# Enchante.net
KiCad netlist of a schematic drawn in Altium Designer
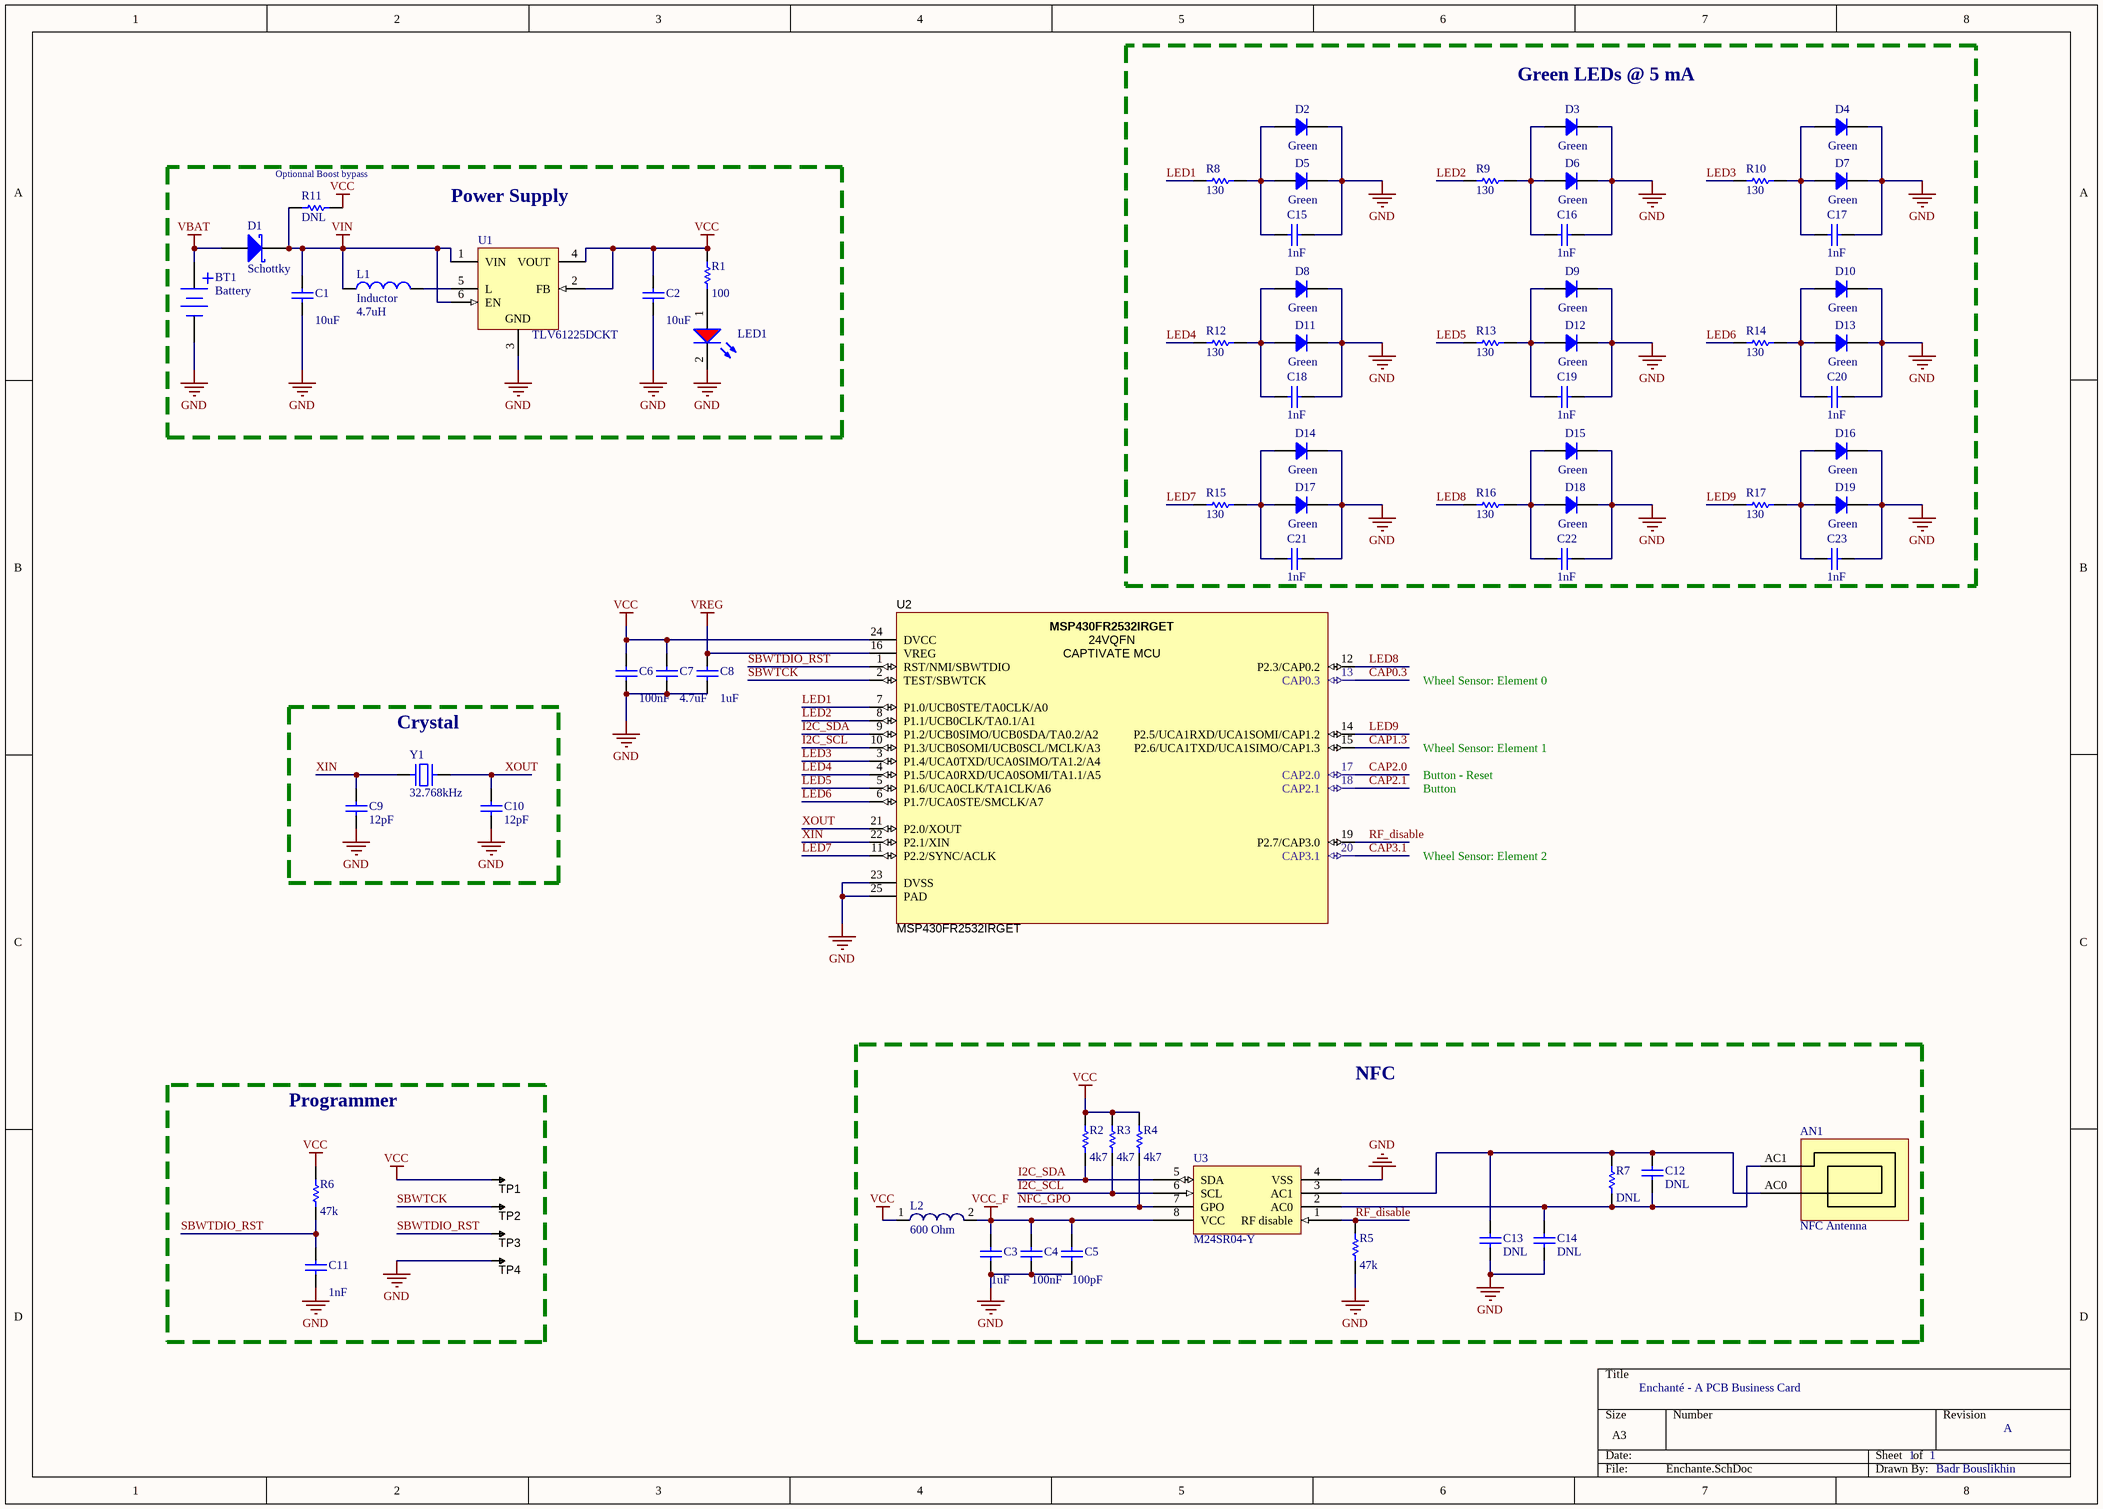
[diagram p0: Enchante.SchDoc]

(export (version "E")
  (design (tool "Eeschema 10.0.6"))
  (components
    (comp (ref "AN1")
      (value "NFC Antenna")
      (footprint "NFC_Antenna")
      (description "L=5.51 uH, tuned for 13.56 MHz")
      (libsource (lib "NFC_Antenna") (part "NFC_Antenna"))
    )
    (comp (ref "BT1")
      (value "Battery")
      (footprint "BC-2001")
      (description "Multicell Battery")
      (libsource (lib "BC-2001") (part "Battery"))
    )
    (comp (ref "C1")
      (value "10uF")
      (footprint "1608[0603]")
      (description "Capacitor")
      (fields (field (name "Comment") "Cap"))
      (libsource (lib "Miscellaneous Devices") (part "Cap"))
    )
    (comp (ref "C2")
      (value "10uF")
      (footprint "1608[0603]")
      (description "Capacitor")
      (fields (field (name "Comment") "Cap"))
      (libsource (lib "Miscellaneous Devices") (part "Cap"))
    )
    (comp (ref "C3")
      (value "1uF")
      (footprint "1608[0603]")
      (description "Capacitor")
      (fields (field (name "Comment") "Cap"))
      (libsource (lib "Miscellaneous Devices") (part "Cap"))
    )
    (comp (ref "C4")
      (value "100nF")
      (footprint "1608[0603]")
      (description "Capacitor")
      (fields (field (name "Comment") "Cap"))
      (libsource (lib "Miscellaneous Devices") (part "Cap"))
    )
    (comp (ref "C5")
      (value "100pF")
      (footprint "1608[0603]")
      (description "Capacitor")
      (fields (field (name "Comment") "Cap"))
      (libsource (lib "Miscellaneous Devices") (part "Cap"))
    )
    (comp (ref "C6")
      (value "100nF")
      (footprint "1608[0603]")
      (description "Capacitor")
      (fields (field (name "Comment") "Cap"))
      (libsource (lib "Miscellaneous Devices") (part "Cap"))
    )
    (comp (ref "C7")
      (value "4.7uF")
      (footprint "1608[0603]")
      (description "Capacitor")
      (fields (field (name "Comment") "Cap"))
      (libsource (lib "Miscellaneous Devices") (part "Cap"))
    )
    (comp (ref "C8")
      (value "1uF")
      (footprint "1608[0603]")
      (description "Capacitor")
      (fields (field (name "Comment") "Cap"))
      (libsource (lib "Miscellaneous Devices") (part "Cap"))
    )
    (comp (ref "C9")
      (value "12pF")
      (footprint "1608[0603]")
      (description "Capacitor")
      (fields (field (name "Comment") "Cap"))
      (libsource (lib "Miscellaneous Devices") (part "Cap"))
    )
    (comp (ref "C10")
      (value "12pF")
      (footprint "1608[0603]")
      (description "Capacitor")
      (fields (field (name "Comment") "Cap"))
      (libsource (lib "Miscellaneous Devices") (part "Cap"))
    )
    (comp (ref "C11")
      (value "1nF")
      (footprint "1608[0603]")
      (description "Capacitor")
      (fields (field (name "Comment") "Cap"))
      (libsource (lib "Miscellaneous Devices") (part "Cap"))
    )
    (comp (ref "C12")
      (value "DNL")
      (footprint "1608[0603]")
      (description "Capacitor")
      (fields (field (name "Comment") "Cap"))
      (libsource (lib "Miscellaneous Devices") (part "Cap"))
    )
    (comp (ref "C13")
      (value "DNL")
      (footprint "1608[0603]")
      (description "Capacitor")
      (fields (field (name "Comment") "Cap"))
      (libsource (lib "Miscellaneous Devices") (part "Cap"))
    )
    (comp (ref "C14")
      (value "DNL")
      (footprint "1608[0603]")
      (description "Capacitor")
      (fields (field (name "Comment") "Cap"))
      (libsource (lib "Miscellaneous Devices") (part "Cap"))
    )
    (comp (ref "C15")
      (value "1nF")
      (footprint "1608[0603]")
      (description "Capacitor")
      (fields (field (name "Comment") "Cap"))
      (libsource (lib "Miscellaneous Devices") (part "Cap"))
    )
    (comp (ref "C16")
      (value "1nF")
      (footprint "1608[0603]")
      (description "Capacitor")
      (fields (field (name "Comment") "Cap"))
      (libsource (lib "Miscellaneous Devices") (part "Cap"))
    )
    (comp (ref "C17")
      (value "1nF")
      (footprint "1608[0603]")
      (description "Capacitor")
      (fields (field (name "Comment") "Cap"))
      (libsource (lib "Miscellaneous Devices") (part "Cap"))
    )
    (comp (ref "C18")
      (value "1nF")
      (footprint "1608[0603]")
      (description "Capacitor")
      (fields (field (name "Comment") "Cap"))
      (libsource (lib "Miscellaneous Devices") (part "Cap"))
    )
    (comp (ref "C19")
      (value "1nF")
      (footprint "1608[0603]")
      (description "Capacitor")
      (fields (field (name "Comment") "Cap"))
      (libsource (lib "Miscellaneous Devices") (part "Cap"))
    )
    (comp (ref "C20")
      (value "1nF")
      (footprint "1608[0603]")
      (description "Capacitor")
      (fields (field (name "Comment") "Cap"))
      (libsource (lib "Miscellaneous Devices") (part "Cap"))
    )
    (comp (ref "C21")
      (value "1nF")
      (footprint "1608[0603]")
      (description "Capacitor")
      (fields (field (name "Comment") "Cap"))
      (libsource (lib "Miscellaneous Devices") (part "Cap"))
    )
    (comp (ref "C22")
      (value "1nF")
      (footprint "1608[0603]")
      (description "Capacitor")
      (fields (field (name "Comment") "Cap"))
      (libsource (lib "Miscellaneous Devices") (part "Cap"))
    )
    (comp (ref "C23")
      (value "1nF")
      (footprint "1608[0603]")
      (description "Capacitor")
      (fields (field (name "Comment") "Cap"))
      (libsource (lib "Miscellaneous Devices") (part "Cap"))
    )
    (comp (ref "D1")
      (value "Schottky")
      (footprint "SOT23_N")
      (description "Schottky Diode")
      (libsource (lib "Miscellaneous Devices") (part "D Schottky"))
    )
    (comp (ref "D2")
      (value "1318243")
      (footprint "LED 0805/2012 GREEN")
      (description "Rectifier Diode")
      (fields (field (name "COLOR") "Green"))
      (libsource (lib "Diodes") (part "Diode"))
    )
    (comp (ref "D3")
      (value "1318243")
      (footprint "LED 0805/2012 GREEN")
      (description "Rectifier Diode")
      (fields (field (name "COLOR") "Green"))
      (libsource (lib "Diodes") (part "Diode"))
    )
    (comp (ref "D4")
      (value "1318243")
      (footprint "LED 0805/2012 GREEN")
      (description "Rectifier Diode")
      (fields (field (name "COLOR") "Green"))
      (libsource (lib "Diodes") (part "Diode"))
    )
    (comp (ref "D5")
      (value "1318243")
      (footprint "LED 0805/2012 GREEN")
      (description "Rectifier Diode")
      (fields (field (name "COLOR") "Green"))
      (libsource (lib "Diodes") (part "Diode"))
    )
    (comp (ref "D6")
      (value "1318243")
      (footprint "LED 0805/2012 GREEN")
      (description "Rectifier Diode")
      (fields (field (name "COLOR") "Green"))
      (libsource (lib "Diodes") (part "Diode"))
    )
    (comp (ref "D7")
      (value "1318243")
      (footprint "LED 0805/2012 GREEN")
      (description "Rectifier Diode")
      (fields (field (name "COLOR") "Green"))
      (libsource (lib "Diodes") (part "Diode"))
    )
    (comp (ref "D8")
      (value "1318243")
      (footprint "LED 0805/2012 GREEN")
      (description "Rectifier Diode")
      (fields (field (name "COLOR") "Green"))
      (libsource (lib "Diodes") (part "Diode"))
    )
    (comp (ref "D9")
      (value "1318243")
      (footprint "LED 0805/2012 GREEN")
      (description "Rectifier Diode")
      (fields (field (name "COLOR") "Green"))
      (libsource (lib "Diodes") (part "Diode"))
    )
    (comp (ref "D10")
      (value "1318243")
      (footprint "LED 0805/2012 GREEN")
      (description "Rectifier Diode")
      (fields (field (name "COLOR") "Green"))
      (libsource (lib "Diodes") (part "Diode"))
    )
    (comp (ref "D11")
      (value "1318243")
      (footprint "LED 0805/2012 GREEN")
      (description "Rectifier Diode")
      (fields (field (name "COLOR") "Green"))
      (libsource (lib "Diodes") (part "Diode"))
    )
    (comp (ref "D12")
      (value "1318243")
      (footprint "LED 0805/2012 GREEN")
      (description "Rectifier Diode")
      (fields (field (name "COLOR") "Green"))
      (libsource (lib "Diodes") (part "Diode"))
    )
    (comp (ref "D13")
      (value "1318243")
      (footprint "LED 0805/2012 GREEN")
      (description "Rectifier Diode")
      (fields (field (name "COLOR") "Green"))
      (libsource (lib "Diodes") (part "Diode"))
    )
    (comp (ref "D14")
      (value "1318243")
      (footprint "LED 0805/2012 GREEN")
      (description "Rectifier Diode")
      (fields (field (name "COLOR") "Green"))
      (libsource (lib "Diodes") (part "Diode"))
    )
    (comp (ref "D15")
      (value "1318243")
      (footprint "LED 0805/2012 GREEN")
      (description "Rectifier Diode")
      (fields (field (name "COLOR") "Green"))
      (libsource (lib "Diodes") (part "Diode"))
    )
    (comp (ref "D16")
      (value "1318243")
      (footprint "LED 0805/2012 GREEN")
      (description "Rectifier Diode")
      (fields (field (name "COLOR") "Green"))
      (libsource (lib "Diodes") (part "Diode"))
    )
    (comp (ref "D17")
      (value "1318243")
      (footprint "LED 0805/2012 GREEN")
      (description "Rectifier Diode")
      (fields (field (name "COLOR") "Green"))
      (libsource (lib "Diodes") (part "Diode"))
    )
    (comp (ref "D18")
      (value "1318243")
      (footprint "LED 0805/2012 GREEN")
      (description "Rectifier Diode")
      (fields (field (name "COLOR") "Green"))
      (libsource (lib "Diodes") (part "Diode"))
    )
    (comp (ref "D19")
      (value "1318243")
      (footprint "LED 0805/2012 GREEN")
      (description "Rectifier Diode")
      (fields (field (name "COLOR") "Green"))
      (libsource (lib "Diodes") (part "Diode"))
    )
    (comp (ref "L1")
      (value "Inductor")
      (footprint "VLS2010E")
      (fields (field (name "ALTIUM_VALUE") "4.7uH"))
      (libsource (lib "Miscellaneous Devices") (part "Inductor"))
    )
    (comp (ref "L2")
      (value "600 Ohm")
      (footprint "SMD 0805")
      (description "SMD EMI Suppression Ferrite Beads WE-CBF, Z= 600 Ohm")
      (fields
        (field (name "PARTNO") "742792042")
        (field (name "MANUFACTURER") "Würth Elektronik eiSos GmbH")
        (field (name "CREATED BY") "Christin Zierenner")
      )
      (libsource (lib "WE-CBF_rev15a") (part "WE-CBF 0805, 742792042"))
    )
    (comp (ref "LED1")
      (value "150060RS75000")
      (footprint "LED_0603_Red")
      (description "SMD mono-color Chip LED, WL-SMCW, Red")
      (fields
        (field (name "MANUFACTURER") "W黵th Elektronik eiSos GmbH")
        (field (name "CREATED BY") "Christin Otto")
      )
      (libsource (lib "WL-SMCW_rev15b") (part "WL-SMCW 0603  150060RS75000"))
    )
    (comp (ref "R1")
      (value "100")
      (footprint "J1-0603")
      (description "Resistor")
      (fields (field (name "Comment") "Res1"))
      (libsource (lib "Miscellaneous Devices") (part "Res1"))
    )
    (comp (ref "R2")
      (value "4k7")
      (footprint "J1-0603")
      (description "Resistor")
      (fields (field (name "Comment") "Res1"))
      (libsource (lib "Miscellaneous Devices") (part "Res1"))
    )
    (comp (ref "R3")
      (value "4k7")
      (footprint "J1-0603")
      (description "Resistor")
      (fields (field (name "Comment") "Res1"))
      (libsource (lib "Miscellaneous Devices") (part "Res1"))
    )
    (comp (ref "R4")
      (value "4k7")
      (footprint "J1-0603")
      (description "Resistor")
      (fields (field (name "Comment") "Res1"))
      (libsource (lib "Miscellaneous Devices") (part "Res1"))
    )
    (comp (ref "R5")
      (value "47k")
      (footprint "J1-0603")
      (description "Resistor")
      (fields (field (name "Comment") "Res1"))
      (libsource (lib "Miscellaneous Devices") (part "Res1"))
    )
    (comp (ref "R6")
      (value "47k")
      (footprint "J1-0603")
      (description "Resistor")
      (fields (field (name "Comment") "Res1"))
      (libsource (lib "Miscellaneous Devices") (part "Res1"))
    )
    (comp (ref "R7")
      (value "DNL")
      (footprint "J1-0603")
      (description "Resistor")
      (fields (field (name "Comment") "Res1"))
      (libsource (lib "Miscellaneous Devices") (part "Res1"))
    )
    (comp (ref "R8")
      (value "130")
      (footprint "J1-0603")
      (description "Resistor")
      (fields (field (name "Comment") "Res1"))
      (libsource (lib "Miscellaneous Devices") (part "Res1"))
    )
    (comp (ref "R9")
      (value "130")
      (footprint "J1-0603")
      (description "Resistor")
      (fields (field (name "Comment") "Res1"))
      (libsource (lib "Miscellaneous Devices") (part "Res1"))
    )
    (comp (ref "R10")
      (value "130")
      (footprint "J1-0603")
      (description "Resistor")
      (fields (field (name "Comment") "Res1"))
      (libsource (lib "Miscellaneous Devices") (part "Res1"))
    )
    (comp (ref "R11")
      (value "DNL")
      (footprint "J1-0603")
      (description "Resistor")
      (fields (field (name "Comment") "Res1"))
      (libsource (lib "Miscellaneous Devices") (part "Res1"))
    )
    (comp (ref "R12")
      (value "130")
      (footprint "J1-0603")
      (description "Resistor")
      (fields (field (name "Comment") "Res1"))
      (libsource (lib "Miscellaneous Devices") (part "Res1"))
    )
    (comp (ref "R13")
      (value "130")
      (footprint "J1-0603")
      (description "Resistor")
      (fields (field (name "Comment") "Res1"))
      (libsource (lib "Miscellaneous Devices") (part "Res1"))
    )
    (comp (ref "R14")
      (value "130")
      (footprint "J1-0603")
      (description "Resistor")
      (fields (field (name "Comment") "Res1"))
      (libsource (lib "Miscellaneous Devices") (part "Res1"))
    )
    (comp (ref "R15")
      (value "130")
      (footprint "J1-0603")
      (description "Resistor")
      (fields (field (name "Comment") "Res1"))
      (libsource (lib "Miscellaneous Devices") (part "Res1"))
    )
    (comp (ref "R16")
      (value "130")
      (footprint "J1-0603")
      (description "Resistor")
      (fields (field (name "Comment") "Res1"))
      (libsource (lib "Miscellaneous Devices") (part "Res1"))
    )
    (comp (ref "R17")
      (value "130")
      (footprint "J1-0603")
      (description "Resistor")
      (fields (field (name "Comment") "Res1"))
      (libsource (lib "Miscellaneous Devices") (part "Res1"))
    )
    (comp (ref "TP1")
      (value "TESTPOINT")
      (footprint "TP-R60")
      (description "SMD test pin")
      (libsource (lib "PBL - Test Points") (part "TESTPOINT"))
    )
    (comp (ref "TP2")
      (value "TESTPOINT")
      (footprint "TP-R60")
      (description "SMD test pin")
      (libsource (lib "PBL - Test Points") (part "TESTPOINT"))
    )
    (comp (ref "TP3")
      (value "TESTPOINT")
      (footprint "TP-R60")
      (description "SMD test pin")
      (libsource (lib "PBL - Test Points") (part "TESTPOINT"))
    )
    (comp (ref "TP4")
      (value "TESTPOINT")
      (footprint "TP-R60")
      (description "SMD test pin")
      (libsource (lib "PBL - Test Points") (part "TESTPOINT"))
    )
    (comp (ref "U1")
      (value "TLV61225DCKT")
      (footprint "DCK0006A_M")
      (fields (field (name "MANUFACTURER") "Texas Instruments"))
      (libsource (lib "Altium Content Vault") (part "CMP-0343-00078-2"))
    )
    (comp (ref "U2")
      (value "MSP430FR2532IRGET")
      (footprint "RGE24_N")
      (description "MSP430 Captivate Microcontroller")
      (fields (field (name "MANUFACTURER") "Texas Instruments") (field (name "SYMBOLCREATOR") "B.B."))
      (libsource (lib "MSP430FR2532") (part "MSP430FR2532IRGET"))
    )
    (comp (ref "U3")
      (value "M24SR04-Y")
      (footprint "ST TSSOP-8")
      (description "Dynamic NFC/RFID tag IC with 4-Kbit EEPROM,   NFC Forum Type 4 Tag and I²C interface")
      (libsource (lib "M24SR04-Y") (part "M24SR04-Y"))
    )
    (comp (ref "Y1")
      (value "32.768kHz")
      (footprint "ABRACON ABS25")
      (description "SMT Crystal")
      (libsource (lib "Crystals") (part "Abracon Crystal ABS25"))
    )
  )
  (nets
    (net (code "1") (name "/CAP0.3") (class "Default")
      (node (ref "U2") (pin "13") (pinfunction "CAP0.3_13") (pintype "bidirectional"))
    )
    (net (code "2") (name "/CAP1.3") (class "Default")
      (node (ref "U2") (pin "15") (pinfunction "P2.6/UCA1TXD/UCA1SIMO/CAP1.3_15") (pintype "bidirectional"))
    )
    (net (code "3") (name "/CAP2.0") (class "Default")
      (node (ref "U2") (pin "17") (pinfunction "CAP2.0_17") (pintype "bidirectional"))
    )
    (net (code "4") (name "/CAP2.1") (class "Default")
      (node (ref "U2") (pin "18") (pinfunction "CAP2.1_18") (pintype "bidirectional"))
    )
    (net (code "5") (name "/CAP3.1") (class "Default")
      (node (ref "U2") (pin "20") (pinfunction "CAP3.1_20") (pintype "bidirectional"))
    )
    (net (code "6") (name "/I2C_SCL") (class "Default")
      (node (ref "R3") (pin "1") (pinfunction "1_1") (pintype "passive"))
      (node (ref "U2") (pin "10") (pinfunction "P1.3/UCB0SOMI/UCB0SCL/MCLK/A3_10") (pintype "bidirectional"))
      (node (ref "U3") (pin "6") (pinfunction "SCL_6") (pintype "input"))
    )
    (net (code "7") (name "/I2C_SDA") (class "Default")
      (node (ref "R2") (pin "1") (pinfunction "1_1") (pintype "passive"))
      (node (ref "U2") (pin "9") (pinfunction "P1.2/UCB0SIMO/UCB0SDA/TA0.2/A2_9") (pintype "bidirectional"))
      (node (ref "U3") (pin "5") (pinfunction "SDA_5") (pintype "bidirectional"))
    )
    (net (code "8") (name "/LED1") (class "Default")
      (node (ref "R8") (pin "2") (pinfunction "2_2") (pintype "passive"))
      (node (ref "U2") (pin "7") (pinfunction "P1.0/UCB0STE/TA0CLK/A0_7") (pintype "bidirectional"))
    )
    (net (code "9") (name "/LED2") (class "Default")
      (node (ref "R9") (pin "2") (pinfunction "2_2") (pintype "passive"))
      (node (ref "U2") (pin "8") (pinfunction "P1.1/UCB0CLK/TA0.1/A1_8") (pintype "bidirectional"))
    )
    (net (code "10") (name "/LED3") (class "Default")
      (node (ref "R10") (pin "2") (pinfunction "2_2") (pintype "passive"))
      (node (ref "U2") (pin "3") (pinfunction "P1.4/UCA0TXD/UCA0SIMO/TA1.2/A4_3") (pintype "bidirectional"))
    )
    (net (code "11") (name "/LED4") (class "Default")
      (node (ref "R12") (pin "2") (pinfunction "2_2") (pintype "passive"))
      (node (ref "U2") (pin "4") (pinfunction "P1.5/UCA0RXD/UCA0SOMI/TA1.1/A5_4") (pintype "bidirectional"))
    )
    (net (code "12") (name "/LED5") (class "Default")
      (node (ref "R13") (pin "2") (pinfunction "2_2") (pintype "passive"))
      (node (ref "U2") (pin "5") (pinfunction "P1.6/UCA0CLK/TA1CLK/A6_5") (pintype "bidirectional"))
    )
    (net (code "13") (name "/LED6") (class "Default")
      (node (ref "R14") (pin "2") (pinfunction "2_2") (pintype "passive"))
      (node (ref "U2") (pin "6") (pinfunction "P1.7/UCA0STE/SMCLK/A7_6") (pintype "bidirectional"))
    )
    (net (code "14") (name "/LED7") (class "Default")
      (node (ref "R15") (pin "2") (pinfunction "2_2") (pintype "passive"))
      (node (ref "U2") (pin "11") (pinfunction "P2.2/SYNC/ACLK_11") (pintype "bidirectional"))
    )
    (net (code "15") (name "/LED8") (class "Default")
      (node (ref "R16") (pin "2") (pinfunction "2_2") (pintype "passive"))
      (node (ref "U2") (pin "12") (pinfunction "P2.3/CAP0.2_12") (pintype "bidirectional"))
    )
    (net (code "16") (name "/LED9") (class "Default")
      (node (ref "R17") (pin "2") (pinfunction "2_2") (pintype "passive"))
      (node (ref "U2") (pin "14") (pinfunction "P2.5/UCA1RXD/UCA1SOMI/CAP1.2_14") (pintype "bidirectional"))
    )
    (net (code "17") (name "/NFC_GPO") (class "Default")
      (node (ref "R4") (pin "1") (pinfunction "1_1") (pintype "passive"))
      (node (ref "U3") (pin "7") (pinfunction "GPO_7") (pintype "passive"))
    )
    (net (code "18") (name "/RF_disable") (class "Default")
      (node (ref "R5") (pin "2") (pinfunction "2_2") (pintype "passive"))
      (node (ref "U2") (pin "19") (pinfunction "P2.7/CAP3.0_19") (pintype "bidirectional"))
      (node (ref "U3") (pin "1") (pinfunction "RF_disable_1") (pintype "input"))
    )
    (net (code "19") (name "/SBWTCK") (class "Default")
      (node (ref "TP2") (pin "1") (pintype "passive"))
      (node (ref "U2") (pin "2") (pinfunction "TEST/SBWTCK_2") (pintype "bidirectional"))
    )
    (net (code "20") (name "/SBWTDIO_RST") (class "Default")
      (node (ref "C11") (pin "2") (pinfunction "2_2") (pintype "passive"))
      (node (ref "R6") (pin "1") (pinfunction "1_1") (pintype "passive"))
      (node (ref "TP3") (pin "1") (pintype "passive"))
      (node (ref "U2") (pin "1") (pinfunction "RST/NMI/SBWTDIO_1") (pintype "bidirectional"))
    )
    (net (code "21") (name "/XIN") (class "Default")
      (node (ref "C9") (pin "2") (pinfunction "2_2") (pintype "passive"))
      (node (ref "U2") (pin "22") (pinfunction "P2.1/XIN_22") (pintype "bidirectional"))
      (node (ref "Y1") (pin "1") (pinfunction "1_1") (pintype "passive"))
    )
    (net (code "22") (name "/XOUT") (class "Default")
      (node (ref "C10") (pin "2") (pinfunction "2_2") (pintype "passive"))
      (node (ref "U2") (pin "21") (pinfunction "P2.0/XOUT_21") (pintype "bidirectional"))
      (node (ref "Y1") (pin "4") (pinfunction "4_4") (pintype "passive"))
    )
    (net (code "23") (name "GND") (class "Default")
      (node (ref "BT1") (pin "2") (pinfunction "-_2") (pintype "passive"))
      (node (ref "C1") (pin "1") (pinfunction "1_1") (pintype "passive"))
      (node (ref "C10") (pin "1") (pinfunction "1_1") (pintype "passive"))
      (node (ref "C11") (pin "1") (pinfunction "1_1") (pintype "passive"))
      (node (ref "C13") (pin "1") (pinfunction "1_1") (pintype "passive"))
      (node (ref "C14") (pin "1") (pinfunction "1_1") (pintype "passive"))
      (node (ref "C15") (pin "1") (pinfunction "1_1") (pintype "passive"))
      (node (ref "C16") (pin "1") (pinfunction "1_1") (pintype "passive"))
      (node (ref "C17") (pin "1") (pinfunction "1_1") (pintype "passive"))
      (node (ref "C18") (pin "1") (pinfunction "1_1") (pintype "passive"))
      (node (ref "C19") (pin "1") (pinfunction "1_1") (pintype "passive"))
      (node (ref "C2") (pin "1") (pinfunction "1_1") (pintype "passive"))
      (node (ref "C20") (pin "1") (pinfunction "1_1") (pintype "passive"))
      (node (ref "C21") (pin "1") (pinfunction "1_1") (pintype "passive"))
      (node (ref "C22") (pin "1") (pinfunction "1_1") (pintype "passive"))
      (node (ref "C23") (pin "1") (pinfunction "1_1") (pintype "passive"))
      (node (ref "C3") (pin "1") (pinfunction "1_1") (pintype "passive"))
      (node (ref "C4") (pin "1") (pinfunction "1_1") (pintype "passive"))
      (node (ref "C5") (pin "1") (pinfunction "1_1") (pintype "passive"))
      (node (ref "C6") (pin "1") (pinfunction "1_1") (pintype "passive"))
      (node (ref "C7") (pin "1") (pinfunction "1_1") (pintype "passive"))
      (node (ref "C8") (pin "1") (pinfunction "1_1") (pintype "passive"))
      (node (ref "C9") (pin "1") (pinfunction "1_1") (pintype "passive"))
      (node (ref "D10") (pin "2") (pinfunction "2_2") (pintype "passive"))
      (node (ref "D11") (pin "2") (pinfunction "2_2") (pintype "passive"))
      (node (ref "D12") (pin "2") (pinfunction "2_2") (pintype "passive"))
      (node (ref "D13") (pin "2") (pinfunction "2_2") (pintype "passive"))
      (node (ref "D14") (pin "2") (pinfunction "2_2") (pintype "passive"))
      (node (ref "D15") (pin "2") (pinfunction "2_2") (pintype "passive"))
      (node (ref "D16") (pin "2") (pinfunction "2_2") (pintype "passive"))
      (node (ref "D17") (pin "2") (pinfunction "2_2") (pintype "passive"))
      (node (ref "D18") (pin "2") (pinfunction "2_2") (pintype "passive"))
      (node (ref "D19") (pin "2") (pinfunction "2_2") (pintype "passive"))
      (node (ref "D2") (pin "2") (pinfunction "2_2") (pintype "passive"))
      (node (ref "D3") (pin "2") (pinfunction "2_2") (pintype "passive"))
      (node (ref "D4") (pin "2") (pinfunction "2_2") (pintype "passive"))
      (node (ref "D5") (pin "2") (pinfunction "2_2") (pintype "passive"))
      (node (ref "D6") (pin "2") (pinfunction "2_2") (pintype "passive"))
      (node (ref "D7") (pin "2") (pinfunction "2_2") (pintype "passive"))
      (node (ref "D8") (pin "2") (pinfunction "2_2") (pintype "passive"))
      (node (ref "D9") (pin "2") (pinfunction "2_2") (pintype "passive"))
      (node (ref "LED1") (pin "2") (pinfunction "C_2") (pintype "passive"))
      (node (ref "R5") (pin "1") (pinfunction "1_1") (pintype "passive"))
      (node (ref "TP4") (pin "1") (pintype "passive"))
      (node (ref "U1") (pin "3") (pinfunction "GND_3") (pintype "power_in"))
      (node (ref "U2") (pin "23") (pinfunction "DVSS_23") (pintype "power_in"))
      (node (ref "U2") (pin "25") (pinfunction "PAD_25") (pintype "power_in"))
      (node (ref "U3") (pin "4") (pinfunction "VSS_4") (pintype "power_in"))
    )
    (net (code "24") (name "Net-(C15-Pad2)") (class "Default")
      (node (ref "C15") (pin "2") (pinfunction "2_2") (pintype "passive"))
      (node (ref "D2") (pin "1") (pinfunction "1_1") (pintype "passive"))
      (node (ref "D5") (pin "1") (pinfunction "1_1") (pintype "passive"))
      (node (ref "R8") (pin "1") (pinfunction "1_1") (pintype "passive"))
    )
    (net (code "25") (name "Net-(C16-Pad2)") (class "Default")
      (node (ref "C16") (pin "2") (pinfunction "2_2") (pintype "passive"))
      (node (ref "D3") (pin "1") (pinfunction "1_1") (pintype "passive"))
      (node (ref "D6") (pin "1") (pinfunction "1_1") (pintype "passive"))
      (node (ref "R9") (pin "1") (pinfunction "1_1") (pintype "passive"))
    )
    (net (code "26") (name "Net-(C17-Pad2)") (class "Default")
      (node (ref "C17") (pin "2") (pinfunction "2_2") (pintype "passive"))
      (node (ref "D4") (pin "1") (pinfunction "1_1") (pintype "passive"))
      (node (ref "D7") (pin "1") (pinfunction "1_1") (pintype "passive"))
      (node (ref "R10") (pin "1") (pinfunction "1_1") (pintype "passive"))
    )
    (net (code "27") (name "Net-(C18-Pad2)") (class "Default")
      (node (ref "C18") (pin "2") (pinfunction "2_2") (pintype "passive"))
      (node (ref "D11") (pin "1") (pinfunction "1_1") (pintype "passive"))
      (node (ref "D8") (pin "1") (pinfunction "1_1") (pintype "passive"))
      (node (ref "R12") (pin "1") (pinfunction "1_1") (pintype "passive"))
    )
    (net (code "28") (name "Net-(C19-Pad2)") (class "Default")
      (node (ref "C19") (pin "2") (pinfunction "2_2") (pintype "passive"))
      (node (ref "D12") (pin "1") (pinfunction "1_1") (pintype "passive"))
      (node (ref "D9") (pin "1") (pinfunction "1_1") (pintype "passive"))
      (node (ref "R13") (pin "1") (pinfunction "1_1") (pintype "passive"))
    )
    (net (code "29") (name "Net-(C20-Pad2)") (class "Default")
      (node (ref "C20") (pin "2") (pinfunction "2_2") (pintype "passive"))
      (node (ref "D10") (pin "1") (pinfunction "1_1") (pintype "passive"))
      (node (ref "D13") (pin "1") (pinfunction "1_1") (pintype "passive"))
      (node (ref "R14") (pin "1") (pinfunction "1_1") (pintype "passive"))
    )
    (net (code "30") (name "Net-(C21-Pad2)") (class "Default")
      (node (ref "C21") (pin "2") (pinfunction "2_2") (pintype "passive"))
      (node (ref "D14") (pin "1") (pinfunction "1_1") (pintype "passive"))
      (node (ref "D17") (pin "1") (pinfunction "1_1") (pintype "passive"))
      (node (ref "R15") (pin "1") (pinfunction "1_1") (pintype "passive"))
    )
    (net (code "31") (name "Net-(C22-Pad2)") (class "Default")
      (node (ref "C22") (pin "2") (pinfunction "2_2") (pintype "passive"))
      (node (ref "D15") (pin "1") (pinfunction "1_1") (pintype "passive"))
      (node (ref "D18") (pin "1") (pinfunction "1_1") (pintype "passive"))
      (node (ref "R16") (pin "1") (pinfunction "1_1") (pintype "passive"))
    )
    (net (code "32") (name "Net-(C23-Pad2)") (class "Default")
      (node (ref "C23") (pin "2") (pinfunction "2_2") (pintype "passive"))
      (node (ref "D16") (pin "1") (pinfunction "1_1") (pintype "passive"))
      (node (ref "D19") (pin "1") (pinfunction "1_1") (pintype "passive"))
      (node (ref "R17") (pin "1") (pinfunction "1_1") (pintype "passive"))
    )
    (net (code "33") (name "Net-(LED1-A)") (class "Default")
      (node (ref "LED1") (pin "1") (pinfunction "A_1") (pintype "passive"))
      (node (ref "R1") (pin "1") (pinfunction "1_1") (pintype "passive"))
    )
    (net (code "34") (name "Net-(U1-L)") (class "Default")
      (node (ref "L1") (pin "2") (pinfunction "2_2") (pintype "passive"))
      (node (ref "U1") (pin "5") (pinfunction "L_5") (pintype "power_in"))
    )
    (net (code "35") (name "Net-(U3-AC0)") (class "Default")
      (node (ref "AN1") (pin "AC1") (pintype "passive"))
      (node (ref "C12") (pin "1") (pinfunction "1_1") (pintype "passive"))
      (node (ref "C14") (pin "2") (pinfunction "2_2") (pintype "passive"))
      (node (ref "R7") (pin "1") (pinfunction "1_1") (pintype "passive"))
      (node (ref "U3") (pin "2") (pinfunction "AC0_2") (pintype "passive"))
    )
    (net (code "36") (name "Net-(U3-AC1)") (class "Default")
      (node (ref "AN1") (pin "AC0") (pintype "passive"))
      (node (ref "C12") (pin "2") (pinfunction "2_2") (pintype "passive"))
      (node (ref "C13") (pin "2") (pinfunction "2_2") (pintype "passive"))
      (node (ref "R7") (pin "2") (pinfunction "2_2") (pintype "passive"))
      (node (ref "U3") (pin "3") (pinfunction "AC1_3") (pintype "passive"))
    )
    (net (code "37") (name "VBAT") (class "Default")
      (node (ref "BT1") (pin "1") (pinfunction "+_1") (pintype "passive"))
      (node (ref "D1") (pin "1") (pinfunction "A_1") (pintype "passive"))
    )
    (net (code "38") (name "VCC") (class "Default")
      (node (ref "C2") (pin "2") (pinfunction "2_2") (pintype "passive"))
      (node (ref "C6") (pin "2") (pinfunction "2_2") (pintype "passive"))
      (node (ref "C7") (pin "2") (pinfunction "2_2") (pintype "passive"))
      (node (ref "L2") (pin "1") (pinfunction "1_1") (pintype "passive"))
      (node (ref "R1") (pin "2") (pinfunction "2_2") (pintype "passive"))
      (node (ref "R11") (pin "1") (pinfunction "1_1") (pintype "passive"))
      (node (ref "R2") (pin "2") (pinfunction "2_2") (pintype "passive"))
      (node (ref "R3") (pin "2") (pinfunction "2_2") (pintype "passive"))
      (node (ref "R4") (pin "2") (pinfunction "2_2") (pintype "passive"))
      (node (ref "R6") (pin "2") (pinfunction "2_2") (pintype "passive"))
      (node (ref "TP1") (pin "1") (pintype "passive"))
      (node (ref "U1") (pin "2") (pinfunction "FB_2") (pintype "input"))
      (node (ref "U1") (pin "4") (pinfunction "VOUT_4") (pintype "power_in"))
      (node (ref "U2") (pin "24") (pinfunction "DVCC_24") (pintype "power_in"))
    )
    (net (code "39") (name "VCC_F") (class "Default")
      (node (ref "C3") (pin "2") (pinfunction "2_2") (pintype "passive"))
      (node (ref "C4") (pin "2") (pinfunction "2_2") (pintype "passive"))
      (node (ref "C5") (pin "2") (pinfunction "2_2") (pintype "passive"))
      (node (ref "L2") (pin "2") (pinfunction "2_2") (pintype "passive"))
      (node (ref "U3") (pin "8") (pinfunction "VCC_8") (pintype "power_in"))
    )
    (net (code "40") (name "VIN") (class "Default")
      (node (ref "C1") (pin "2") (pinfunction "2_2") (pintype "passive"))
      (node (ref "D1") (pin "2") (pinfunction "K_2") (pintype "passive"))
      (node (ref "L1") (pin "1") (pinfunction "1_1") (pintype "passive"))
      (node (ref "R11") (pin "2") (pinfunction "2_2") (pintype "passive"))
      (node (ref "U1") (pin "1") (pinfunction "VIN_1") (pintype "power_in"))
      (node (ref "U1") (pin "6") (pinfunction "EN_6") (pintype "input"))
    )
    (net (code "41") (name "VREG") (class "Default")
      (node (ref "C8") (pin "2") (pinfunction "2_2") (pintype "passive"))
      (node (ref "U2") (pin "16") (pinfunction "VREG_16") (pintype "power_in"))
    )
  )
)
